# Mirtle_Pico_Hotec_drv8833_pi.net
KiCad netlist of a schematic drawn in EAGLE
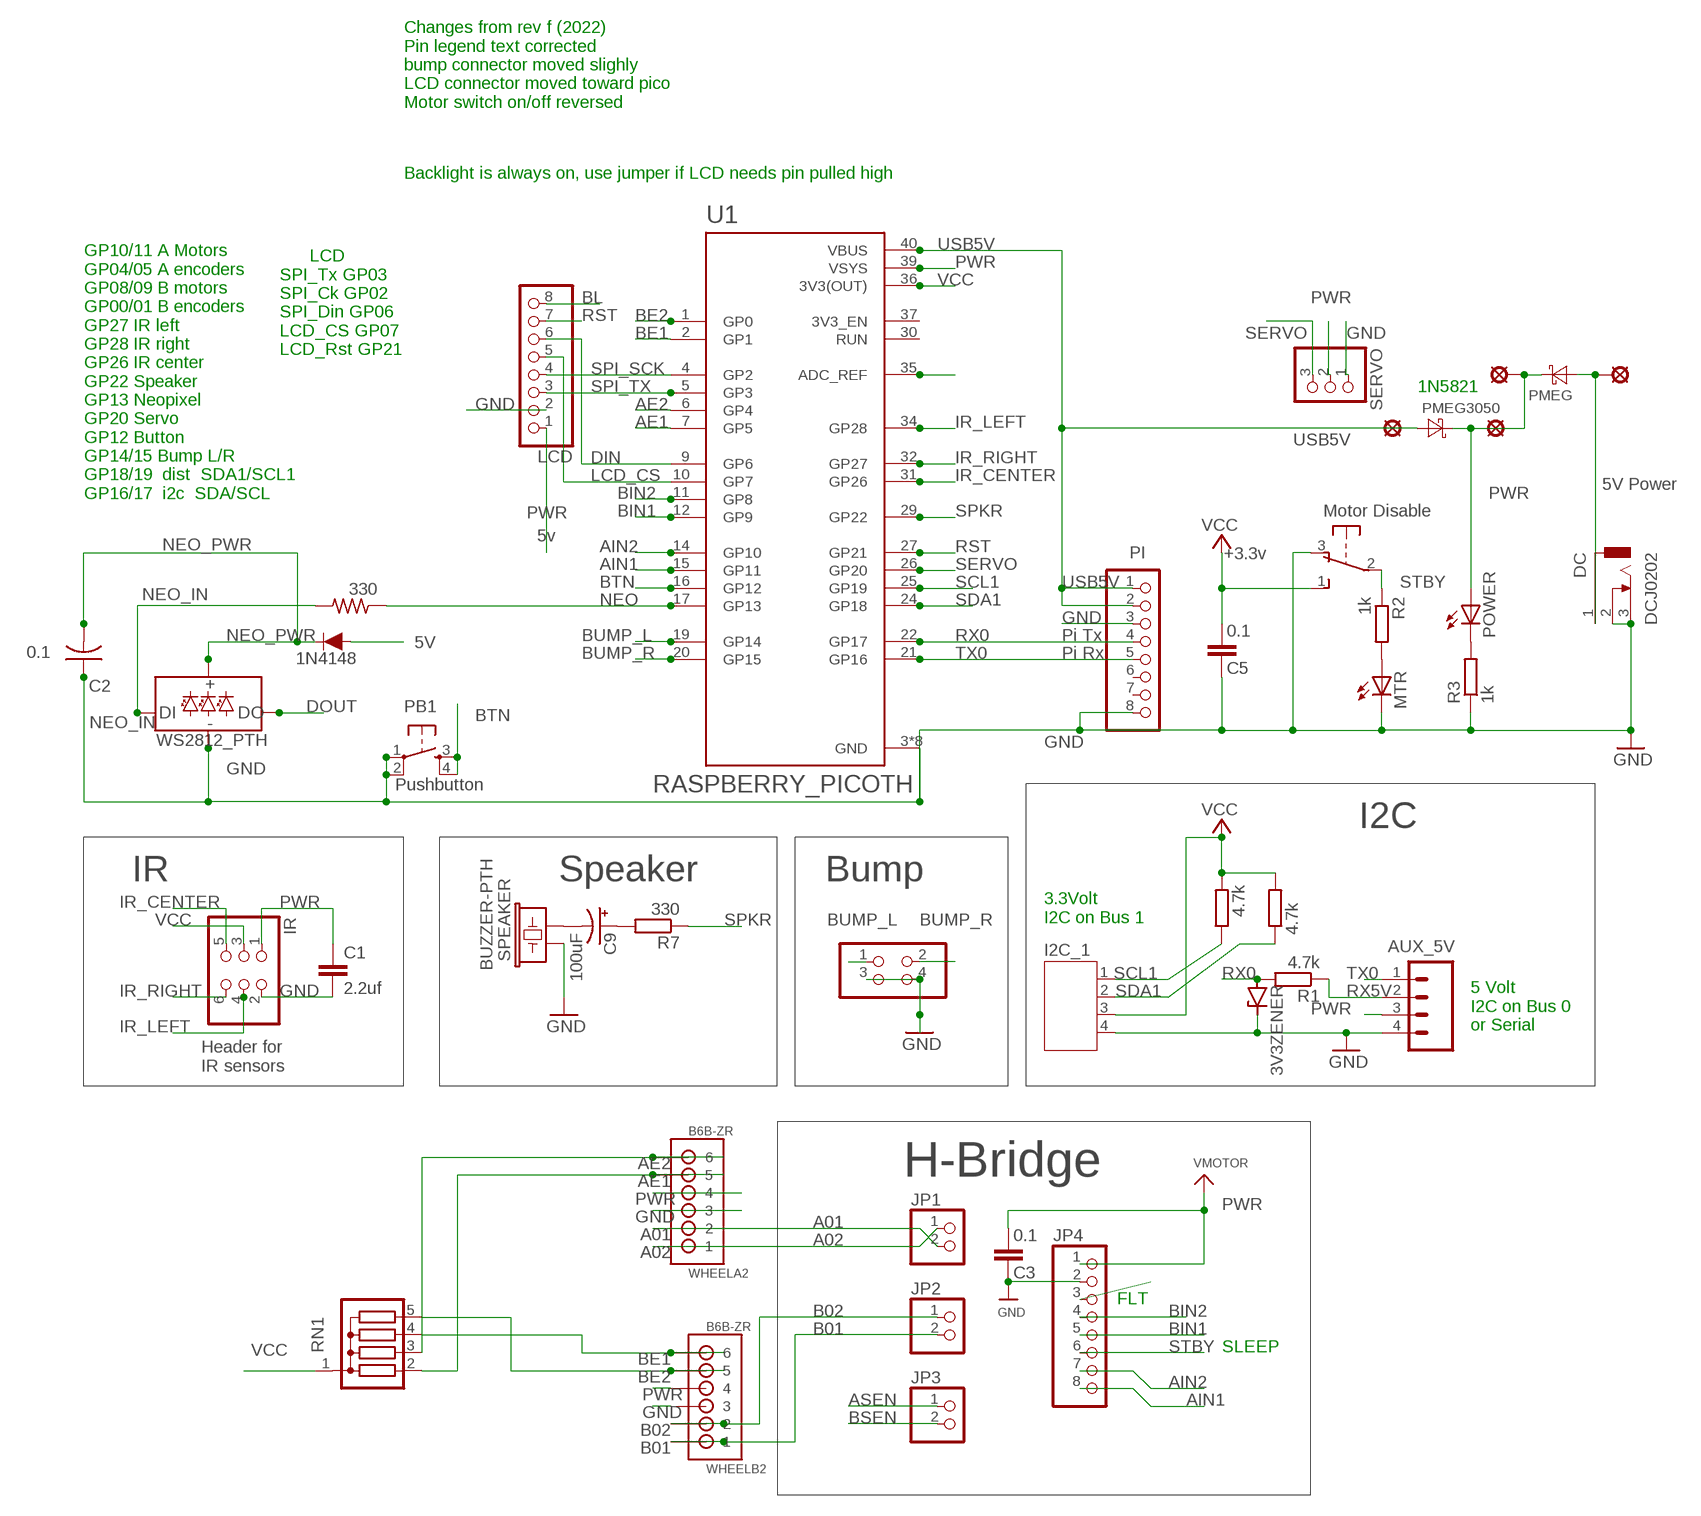
[diagram p0: schematic, sheet 1]

(export (version "E")
  (design (tool "Eeschema 10.0.6"))
  (components
    (comp (ref "3V3ZENER")
      (value "ZENER-DIODEZD-5")
      (footprint "eagle-import:ZDIO-5")
      (libsource (lib "eagle-import") (part "ZENER-DIODEZD-5"))
    )
    (comp (ref "AUX_5V")
      (value "CONN_04")
      (footprint "eagle-import:1X04")
      (libsource (lib "eagle-import") (part "CONN_04"))
    )
    (comp (ref "BUMP")
      (value "PINHD-2X2")
      (footprint "eagle-import:2X02")
      (libsource (lib "eagle-import") (part "PINHD-2X2"))
    )
    (comp (ref "C1")
      (value "2.2uf")
      (footprint "eagle-import:C5B2.5")
      (libsource (lib "eagle-import") (part "C5/2.5"))
    )
    (comp (ref "C2")
      (value "0.1")
      (footprint "eagle-import:C025-024X044")
      (libsource (lib "eagle-import") (part "C-US025-024X044"))
    )
    (comp (ref "C3")
      (value "0.1")
      (footprint "eagle-import:CAP-PTH-SMALLEZ")
      (libsource (lib "eagle-import") (part "CAPEZ"))
    )
    (comp (ref "C5")
      (value "0.1")
      (footprint "eagle-import:CAP-PTH-SMALLEZ")
      (libsource (lib "eagle-import") (part "CAPEZ"))
    )
    (comp (ref "C9")
      (value "100uF")
      (footprint "eagle-import:E2,5-5")
      (libsource (lib "eagle-import") (part "CPOL-USE2.5-5"))
    )
    (comp (ref "D1")
      (value "WS2812_PTH")
      (footprint "eagle-import:WS2812B-PTH-KIT")
      (libsource (lib "eagle-import") (part "WS2812_PTH"))
    )
    (comp (ref "DC")
      (value "DCJ0202")
      (footprint "eagle-import:DCJ0202")
      (libsource (lib "eagle-import") (part "DCJ0202"))
    )
    (comp (ref "I2C_1")
      (value "JST-PH4")
      (footprint "eagle-import:JST-PH4")
      (libsource (lib "eagle-import") (part "JST-PH4"))
    )
    (comp (ref "IN4148")
      (value "200mA/100V/1V")
      (footprint "eagle-import:DIODE-1N4148")
      (libsource (lib "eagle-import") (part "DIODE-1N4148"))
    )
    (comp (ref "IR")
      (value "PINHD-2X3")
      (footprint "eagle-import:2X03")
      (libsource (lib "eagle-import") (part "PINHD-2X3"))
    )
    (comp (ref "JP1")
      (value "HEADER-1X2ROUND")
      (footprint "eagle-import:1X02_ROUND")
      (libsource (lib "eagle-import") (part "HEADER-1X2ROUND"))
    )
    (comp (ref "JP2")
      (value "HEADER-1X2ROUND")
      (footprint "eagle-import:1X02_ROUND")
      (libsource (lib "eagle-import") (part "HEADER-1X2ROUND"))
    )
    (comp (ref "JP3")
      (value "HEADER-1X2ROUND")
      (footprint "eagle-import:1X02_ROUND")
      (libsource (lib "eagle-import") (part "HEADER-1X2ROUND"))
    )
    (comp (ref "JP4")
      (value "HEADER-1X870MIL")
      (footprint "eagle-import:1X08_ROUND_70")
      (libsource (lib "eagle-import") (part "HEADER-1X870MIL"))
    )
    (comp (ref "LCD")
      (value "PINHD-1X8BIG")
      (footprint "eagle-import:1X08-BIG")
      (libsource (lib "eagle-import") (part "PINHD-1X8BIG"))
    )
    (comp (ref "LSP1")
      (value "SE14")
      (footprint "eagle-import:SE14")
      (libsource (lib "eagle-import") (part "SE14"))
    )
    (comp (ref "LSP2")
      (value "SE14")
      (footprint "eagle-import:SE14")
      (libsource (lib "eagle-import") (part "SE14"))
    )
    (comp (ref "LSP3")
      (value "SE14")
      (footprint "eagle-import:SE14")
      (libsource (lib "eagle-import") (part "SE14"))
    )
    (comp (ref "LSP4")
      (value "SE14")
      (footprint "eagle-import:SE14")
      (libsource (lib "eagle-import") (part "SE14"))
    )
    (comp (ref "MTR")
      (value "LED3MM")
      (footprint "eagle-import:LED3MM")
      (libsource (lib "eagle-import") (part "LED3MM"))
    )
    (comp (ref "PB1")
      (value "TAC_SWITCHPTH")
      (footprint "eagle-import:TACTILE-PTH")
      (libsource (lib "eagle-import") (part "TAC_SWITCHPTH"))
    )
    (comp (ref "PI")
      (value "PINHD-1X8BIG")
      (footprint "eagle-import:1X08-BIG")
      (libsource (lib "eagle-import") (part "PINHD-1X8BIG"))
    )
    (comp (ref "PMEG")
      (value "DIODE-SCHOTTKY-SMA")
      (footprint "eagle-import:SMA")
      (libsource (lib "eagle-import") (part "DIODE-SCHOTTKY-SMA"))
    )
    (comp (ref "PMEG3050")
      (value "DIODE-SCHOTTKY-SMA")
      (footprint "eagle-import:SMA")
      (libsource (lib "eagle-import") (part "DIODE-SCHOTTKY-SMA"))
    )
    (comp (ref "POWER")
      (value "LED3MM")
      (footprint "eagle-import:LED3MM")
      (libsource (lib "eagle-import") (part "LED3MM"))
    )
    (comp (ref "R1")
      (value "4.7k")
      (footprint "eagle-import:0204_5")
      (libsource (lib "eagle-import") (part "R-EU_0204/5"))
    )
    (comp (ref "R2")
      (value "1k")
      (footprint "eagle-import:0204_5")
      (libsource (lib "eagle-import") (part "R-EU_0204/5"))
    )
    (comp (ref "R3")
      (value "1k")
      (footprint "eagle-import:0204_5")
      (libsource (lib "eagle-import") (part "R-EU_0204/5"))
    )
    (comp (ref "R4")
      (value "4.7k")
      (footprint "eagle-import:0204_5")
      (libsource (lib "eagle-import") (part "R-EU_0204/5"))
    )
    (comp (ref "R5")
      (value "4.7k")
      (footprint "eagle-import:0204_5")
      (libsource (lib "eagle-import") (part "R-EU_0204/5"))
    )
    (comp (ref "R7")
      (value "330")
      (footprint "eagle-import:0204_5")
      (libsource (lib "eagle-import") (part "R-EU_0204/5"))
    )
    (comp (ref "R12")
      (value "330")
      (footprint "eagle-import:0204_5")
      (libsource (lib "eagle-import") (part "R-US_0204/5"))
    )
    (comp (ref "RN1")
      (value "G04R")
      (footprint "eagle-import:SIL5")
      (libsource (lib "eagle-import") (part "G04R"))
    )
    (comp (ref "SERVO")
      (value "PINHD-1X3")
      (footprint "eagle-import:1X03")
      (libsource (lib "eagle-import") (part "PINHD-1X3"))
    )
    (comp (ref "SPEAKER")
      (value "BUZZER-PTH")
      (footprint "eagle-import:BUZZER-12MM")
      (libsource (lib "eagle-import") (part "BUZZER-PTH"))
    )
    (comp (ref "SW1")
      (value "OS102011MA1Q")
      (footprint "eagle-import:OS102011MA1Q")
      (libsource (lib "eagle-import") (part "OS102011MA1Q"))
    )
    (comp (ref "U1")
      (value "RASPBERRY_PICOTH")
      (footprint "eagle-import:PICO-PKG-TH_MM")
      (libsource (lib "eagle-import") (part "RASPBERRY_PICOTH"))
    )
    (comp (ref "WHEELA2")
      (value "B6B-ZR")
      (footprint "eagle-import:B6B-ZR")
      (libsource (lib "eagle-import") (part "B6B-ZR"))
    )
    (comp (ref "WHEELB2")
      (value "B6B-ZR")
      (footprint "eagle-import:B6B-ZR")
      (libsource (lib "eagle-import") (part "B6B-ZR"))
    )
  )
  (nets
    (net (code "1") (name "/A01") (class "Default")
      (node (ref "JP1") (pin "2") (pinfunction "2_2") (pintype "passive"))
      (node (ref "WHEELA2") (pin "2") (pinfunction "2_2") (pintype "bidirectional"))
    )
    (net (code "2") (name "/A02") (class "Default")
      (node (ref "JP1") (pin "1") (pinfunction "1_1") (pintype "passive"))
      (node (ref "WHEELA2") (pin "1") (pinfunction "1_1") (pintype "bidirectional"))
    )
    (net (code "3") (name "/AE1") (class "Default")
      (node (ref "RN1") (pin "2") (pinfunction "2_2") (pintype "passive"))
      (node (ref "U1") (pin "7") (pinfunction "GP5_7") (pintype "bidirectional"))
      (node (ref "WHEELA2") (pin "5") (pinfunction "5_5") (pintype "bidirectional"))
    )
    (net (code "4") (name "/AE2") (class "Default")
      (node (ref "RN1") (pin "3") (pinfunction "3_3") (pintype "passive"))
      (node (ref "U1") (pin "6") (pinfunction "GP4_6") (pintype "bidirectional"))
      (node (ref "WHEELA2") (pin "6") (pinfunction "6_6") (pintype "bidirectional"))
    )
    (net (code "5") (name "/AIN1") (class "Default")
      (node (ref "JP4") (pin "8") (pinfunction "8_8") (pintype "passive"))
      (node (ref "U1") (pin "15") (pinfunction "GP11_15") (pintype "bidirectional"))
    )
    (net (code "6") (name "/AIN2") (class "Default")
      (node (ref "JP4") (pin "7") (pinfunction "7_7") (pintype "passive"))
      (node (ref "U1") (pin "14") (pinfunction "GP10_14") (pintype "bidirectional"))
    )
    (net (code "7") (name "/ASEN") (class "Default")
      (node (ref "JP3") (pin "1") (pinfunction "1_1") (pintype "passive"))
    )
    (net (code "8") (name "/B01") (class "Default")
      (node (ref "JP2") (pin "2") (pinfunction "2_2") (pintype "passive"))
      (node (ref "WHEELB2") (pin "1") (pinfunction "1_1") (pintype "bidirectional"))
    )
    (net (code "9") (name "/B02") (class "Default")
      (node (ref "JP2") (pin "1") (pinfunction "1_1") (pintype "passive"))
      (node (ref "WHEELB2") (pin "2") (pinfunction "2_2") (pintype "bidirectional"))
    )
    (net (code "10") (name "/BE1") (class "Default")
      (node (ref "RN1") (pin "4") (pinfunction "4_4") (pintype "passive"))
      (node (ref "U1") (pin "2") (pinfunction "GP1_2") (pintype "bidirectional"))
      (node (ref "WHEELB2") (pin "6") (pinfunction "6_6") (pintype "bidirectional"))
    )
    (net (code "11") (name "/BE2") (class "Default")
      (node (ref "RN1") (pin "5") (pinfunction "5_5") (pintype "passive"))
      (node (ref "U1") (pin "1") (pinfunction "GP0_1") (pintype "bidirectional"))
      (node (ref "WHEELB2") (pin "5") (pinfunction "5_5") (pintype "bidirectional"))
    )
    (net (code "12") (name "/BIN1") (class "Default")
      (node (ref "JP4") (pin "5") (pinfunction "5_5") (pintype "passive"))
      (node (ref "U1") (pin "12") (pinfunction "GP9_12") (pintype "bidirectional"))
    )
    (net (code "13") (name "/BIN2") (class "Default")
      (node (ref "JP4") (pin "4") (pinfunction "4_4") (pintype "passive"))
      (node (ref "U1") (pin "11") (pinfunction "GP8_11") (pintype "bidirectional"))
    )
    (net (code "14") (name "/BL") (class "Default")
      (node (ref "LCD") (pin "8") (pinfunction "8_8") (pintype "passive"))
    )
    (net (code "15") (name "/BSEN") (class "Default")
      (node (ref "JP3") (pin "2") (pinfunction "2_2") (pintype "passive"))
    )
    (net (code "16") (name "/BTN") (class "Default")
      (node (ref "PB1") (pin "3") (pinfunction "3_3") (pintype "passive"))
      (node (ref "PB1") (pin "4") (pinfunction "4_4") (pintype "passive"))
      (node (ref "U1") (pin "16") (pinfunction "GP12_16") (pintype "bidirectional"))
    )
    (net (code "17") (name "/BUMP_L") (class "Default")
      (node (ref "BUMP") (pin "1") (pinfunction "1_1") (pintype "passive"))
      (node (ref "U1") (pin "19") (pinfunction "GP14_19") (pintype "bidirectional"))
    )
    (net (code "18") (name "/BUMP_R") (class "Default")
      (node (ref "BUMP") (pin "2") (pinfunction "2_2") (pintype "passive"))
      (node (ref "U1") (pin "20") (pinfunction "GP15_20") (pintype "bidirectional"))
    )
    (net (code "19") (name "/DIN") (class "Default")
      (node (ref "LCD") (pin "6") (pinfunction "6_6") (pintype "passive"))
      (node (ref "U1") (pin "9") (pinfunction "GP6_9") (pintype "bidirectional"))
    )
    (net (code "20") (name "/DOUT") (class "Default")
      (node (ref "D1") (pin "DO") (pinfunction "DO_DO") (pintype "bidirectional"))
    )
    (net (code "21") (name "/IR_CENTER") (class "Default")
      (node (ref "IR") (pin "5") (pinfunction "5_5") (pintype "passive"))
      (node (ref "U1") (pin "31") (pinfunction "GP26_31") (pintype "bidirectional"))
    )
    (net (code "22") (name "/IR_LEFT") (class "Default")
      (node (ref "IR") (pin "4") (pinfunction "4_4") (pintype "passive"))
      (node (ref "U1") (pin "34") (pinfunction "GP28_34") (pintype "bidirectional"))
    )
    (net (code "23") (name "/IR_RIGHT") (class "Default")
      (node (ref "IR") (pin "6") (pinfunction "6_6") (pintype "passive"))
      (node (ref "U1") (pin "32") (pinfunction "GP27_32") (pintype "bidirectional"))
    )
    (net (code "24") (name "/LCD_CS") (class "Default")
      (node (ref "LCD") (pin "5") (pinfunction "5_5") (pintype "passive"))
      (node (ref "U1") (pin "10") (pinfunction "GP7_10") (pintype "bidirectional"))
    )
    (net (code "25") (name "/NEO") (class "Default")
      (node (ref "R12") (pin "1") (pinfunction "1_1") (pintype "passive"))
      (node (ref "U1") (pin "17") (pinfunction "GP13_17") (pintype "bidirectional"))
    )
    (net (code "26") (name "/NEO_IN") (class "Default")
      (node (ref "D1") (pin "DI") (pinfunction "DI_DI") (pintype "bidirectional"))
      (node (ref "R12") (pin "2") (pinfunction "2_2") (pintype "passive"))
    )
    (net (code "27") (name "/NEO_PWR") (class "Default")
      (node (ref "C2") (pin "2") (pinfunction "2_2") (pintype "passive"))
      (node (ref "D1") (pin "VCC") (pinfunction "VCC_VCC") (pintype "bidirectional"))
      (node (ref "IN4148") (pin "C") (pinfunction "C_C") (pintype "passive"))
    )
    (net (code "28") (name "/RST") (class "Default")
      (node (ref "LCD") (pin "7") (pinfunction "7_7") (pintype "passive"))
      (node (ref "U1") (pin "27") (pinfunction "GP21_27") (pintype "bidirectional"))
    )
    (net (code "29") (name "/RX0") (class "Default")
      (node (ref "3V3ZENER") (pin "A") (pinfunction "A_A") (pintype "passive"))
      (node (ref "PI") (pin "4") (pinfunction "4_4") (pintype "passive"))
      (node (ref "R1") (pin "2") (pinfunction "2_2") (pintype "passive"))
      (node (ref "U1") (pin "22") (pinfunction "GP17_22") (pintype "bidirectional"))
    )
    (net (code "30") (name "/RX5V") (class "Default")
      (node (ref "AUX_5V") (pin "2") (pinfunction "2_2") (pintype "passive"))
      (node (ref "R1") (pin "1") (pinfunction "1_1") (pintype "passive"))
    )
    (net (code "31") (name "/SCL1") (class "Default")
      (node (ref "I2C_1") (pin "1") (pinfunction "1_1") (pintype "passive"))
      (node (ref "R5") (pin "1") (pinfunction "1_1") (pintype "passive"))
      (node (ref "U1") (pin "25") (pinfunction "GP19_25") (pintype "bidirectional"))
    )
    (net (code "32") (name "/SDA1") (class "Default")
      (node (ref "I2C_1") (pin "2") (pinfunction "2_2") (pintype "passive"))
      (node (ref "R4") (pin "1") (pinfunction "1_1") (pintype "passive"))
      (node (ref "U1") (pin "24") (pinfunction "GP18_24") (pintype "bidirectional"))
    )
    (net (code "33") (name "/SERVO") (class "Default")
      (node (ref "SERVO") (pin "3") (pinfunction "3_3") (pintype "passive"))
      (node (ref "U1") (pin "26") (pinfunction "GP20_26") (pintype "bidirectional"))
    )
    (net (code "34") (name "/SPI_SCK") (class "Default")
      (node (ref "LCD") (pin "4") (pinfunction "4_4") (pintype "passive"))
      (node (ref "U1") (pin "4") (pinfunction "GP2_4") (pintype "bidirectional"))
    )
    (net (code "35") (name "/SPI_TX") (class "Default")
      (node (ref "LCD") (pin "3") (pinfunction "3_3") (pintype "passive"))
      (node (ref "U1") (pin "5") (pinfunction "GP3_5") (pintype "bidirectional"))
    )
    (net (code "36") (name "/SPKR") (class "Default")
      (node (ref "R7") (pin "1") (pinfunction "1_1") (pintype "passive"))
      (node (ref "U1") (pin "29") (pinfunction "GP22_29") (pintype "bidirectional"))
    )
    (net (code "37") (name "/STBY") (class "Default")
      (node (ref "JP4") (pin "6") (pinfunction "6_6") (pintype "passive"))
      (node (ref "R2") (pin "1") (pinfunction "1_1") (pintype "passive"))
      (node (ref "SW1") (pin "2") (pinfunction "P_2") (pintype "passive"))
    )
    (net (code "38") (name "/TX0") (class "Default")
      (node (ref "AUX_5V") (pin "1") (pinfunction "1_1") (pintype "passive"))
      (node (ref "PI") (pin "5") (pinfunction "5_5") (pintype "passive"))
      (node (ref "U1") (pin "21") (pinfunction "GP16_21") (pintype "bidirectional"))
    )
    (net (code "39") (name "/USB5V") (class "Default")
      (node (ref "LSP1") (pin "MP") (pinfunction "MP_MP") (pintype "passive"))
      (node (ref "PI") (pin "1") (pinfunction "1_1") (pintype "passive"))
      (node (ref "PI") (pin "2") (pinfunction "2_2") (pintype "passive"))
      (node (ref "PMEG3050") (pin "A") (pinfunction "A_A") (pintype "passive"))
      (node (ref "U1") (pin "40") (pinfunction "VBUS_40") (pintype "power_in"))
    )
    (net (code "40") (name "GND") (class "Default")
      (node (ref "3V3ZENER") (pin "C") (pinfunction "C_C") (pintype "passive"))
      (node (ref "AUX_5V") (pin "4") (pinfunction "4_4") (pintype "passive"))
      (node (ref "BUMP") (pin "3") (pinfunction "3_3") (pintype "passive"))
      (node (ref "BUMP") (pin "4") (pinfunction "4_4") (pintype "passive"))
      (node (ref "C1") (pin "2") (pinfunction "2_2") (pintype "passive"))
      (node (ref "C2") (pin "1") (pinfunction "1_1") (pintype "passive"))
      (node (ref "C3") (pin "1") (pinfunction "1_1") (pintype "passive"))
      (node (ref "C5") (pin "1") (pinfunction "1_1") (pintype "passive"))
      (node (ref "D1") (pin "GND") (pinfunction "GND_GND") (pintype "bidirectional"))
      (node (ref "DC") (pin "2") (pinfunction "2_2") (pintype "passive"))
      (node (ref "DC") (pin "3") (pinfunction "3_3") (pintype "passive"))
      (node (ref "I2C_1") (pin "4") (pinfunction "4_4") (pintype "passive"))
      (node (ref "IR") (pin "2") (pinfunction "2_2") (pintype "passive"))
      (node (ref "JP4") (pin "2") (pinfunction "2_2") (pintype "passive"))
      (node (ref "LCD") (pin "2") (pinfunction "2_2") (pintype "passive"))
      (node (ref "MTR") (pin "K") (pinfunction "C_K") (pintype "passive"))
      (node (ref "PB1") (pin "1") (pinfunction "1_1") (pintype "passive"))
      (node (ref "PB1") (pin "2") (pinfunction "2_2") (pintype "passive"))
      (node (ref "PI") (pin "3") (pinfunction "3_3") (pintype "passive"))
      (node (ref "PI") (pin "8") (pinfunction "8_8") (pintype "passive"))
      (node (ref "R3") (pin "1") (pinfunction "1_1") (pintype "passive"))
      (node (ref "SERVO") (pin "1") (pinfunction "1_1") (pintype "passive"))
      (node (ref "SPEAKER") (pin "+") (pinfunction "1_+") (pintype "passive"))
      (node (ref "SW1") (pin "3") (pinfunction "O_3") (pintype "passive"))
      (node (ref "U1") (pin "13") (pinfunction "GND_13") (pintype "power_in"))
      (node (ref "U1") (pin "18") (pinfunction "GND_18") (pintype "power_in"))
      (node (ref "U1") (pin "23") (pinfunction "GND_23") (pintype "power_in"))
      (node (ref "U1") (pin "28") (pinfunction "GND_28") (pintype "power_in"))
      (node (ref "U1") (pin "3") (pinfunction "GND_3") (pintype "power_in"))
      (node (ref "U1") (pin "33") (pinfunction "GND_33") (pintype "power_in"))
      (node (ref "U1") (pin "38") (pinfunction "GND_38") (pintype "power_in"))
      (node (ref "U1") (pin "8") (pinfunction "GND_8") (pintype "power_in"))
      (node (ref "WHEELA2") (pin "3") (pinfunction "3_3") (pintype "bidirectional"))
      (node (ref "WHEELB2") (pin "3") (pinfunction "3_3") (pintype "bidirectional"))
    )
    (net (code "41") (name "Net-(C9-Pad+)") (class "Default")
      (node (ref "C9") (pin "+") (pinfunction "+_+") (pintype "passive"))
      (node (ref "R7") (pin "2") (pinfunction "2_2") (pintype "passive"))
    )
    (net (code "42") (name "Net-(DC-Pad1)") (class "Default")
      (node (ref "DC") (pin "1") (pinfunction "1_1") (pintype "passive"))
      (node (ref "LSP3") (pin "MP") (pinfunction "MP_MP") (pintype "passive"))
      (node (ref "PMEG") (pin "A") (pinfunction "A_A") (pintype "passive"))
    )
    (net (code "43") (name "Net-(MTR-PadA)") (class "Default")
      (node (ref "MTR") (pin "A") (pinfunction "A_A") (pintype "passive"))
      (node (ref "R2") (pin "2") (pinfunction "2_2") (pintype "passive"))
    )
    (net (code "44") (name "Net-(POWER-C)") (class "Default")
      (node (ref "POWER") (pin "K") (pinfunction "C_K") (pintype "passive"))
      (node (ref "R3") (pin "2") (pinfunction "2_2") (pintype "passive"))
    )
    (net (code "45") (name "Net-(SPEAKER-2)") (class "Default")
      (node (ref "C9") (pin "-") (pinfunction "-_-") (pintype "passive"))
      (node (ref "SPEAKER") (pin "-") (pinfunction "2_-") (pintype "passive"))
    )
    (net (code "46") (name "VCC") (class "Default")
      (node (ref "C5") (pin "2") (pinfunction "2_2") (pintype "passive"))
      (node (ref "I2C_1") (pin "3") (pinfunction "3_3") (pintype "passive"))
      (node (ref "IR") (pin "3") (pinfunction "3_3") (pintype "passive"))
      (node (ref "R4") (pin "2") (pinfunction "2_2") (pintype "passive"))
      (node (ref "R5") (pin "2") (pinfunction "2_2") (pintype "passive"))
      (node (ref "RN1") (pin "1") (pinfunction "1_1") (pintype "passive"))
      (node (ref "SW1") (pin "1") (pinfunction "S_1") (pintype "passive"))
      (node (ref "U1") (pin "36") (pinfunction "3V3(OUT)_36") (pintype "power_in"))
    )
    (net (code "47") (name "VMOTOR") (class "Default")
      (node (ref "AUX_5V") (pin "3") (pinfunction "3_3") (pintype "passive"))
      (node (ref "C1") (pin "1") (pinfunction "1_1") (pintype "passive"))
      (node (ref "C3") (pin "2") (pinfunction "2_2") (pintype "passive"))
      (node (ref "IN4148") (pin "A") (pinfunction "A_A") (pintype "passive"))
      (node (ref "IR") (pin "1") (pinfunction "1_1") (pintype "passive"))
      (node (ref "JP4") (pin "1") (pinfunction "1_1") (pintype "passive"))
      (node (ref "LCD") (pin "1") (pinfunction "1_1") (pintype "passive"))
      (node (ref "LSP2") (pin "MP") (pinfunction "MP_MP") (pintype "passive"))
      (node (ref "LSP4") (pin "MP") (pinfunction "MP_MP") (pintype "passive"))
      (node (ref "PMEG") (pin "C") (pinfunction "C_C") (pintype "passive"))
      (node (ref "PMEG3050") (pin "C") (pinfunction "C_C") (pintype "passive"))
      (node (ref "POWER") (pin "A") (pinfunction "A_A") (pintype "passive"))
      (node (ref "SERVO") (pin "2") (pinfunction "2_2") (pintype "passive"))
      (node (ref "U1") (pin "39") (pinfunction "VSYS_39") (pintype "power_in"))
      (node (ref "WHEELA2") (pin "4") (pinfunction "4_4") (pintype "bidirectional"))
      (node (ref "WHEELB2") (pin "4") (pinfunction "4_4") (pintype "bidirectional"))
    )
    (net (code "48") (name "unconnected-(JP4-Pad3)") (class "Default")
      (node (ref "JP4") (pin "3") (pinfunction "3_3") (pintype "passive"))
    )
    (net (code "49") (name "unconnected-(PI-Pad6)") (class "Default")
      (node (ref "PI") (pin "6") (pinfunction "6_6") (pintype "passive"))
    )
    (net (code "50") (name "unconnected-(PI-Pad7)") (class "Default")
      (node (ref "PI") (pin "7") (pinfunction "7_7") (pintype "passive"))
    )
    (net (code "51") (name "unconnected-(U1-3V3_EN-Pad37)") (class "Default")
      (node (ref "U1") (pin "37") (pinfunction "3V3_EN_37") (pintype "input"))
    )
    (net (code "52") (name "unconnected-(U1-ADC_REF-Pad35)") (class "Default")
      (node (ref "U1") (pin "35") (pinfunction "ADC_REF_35") (pintype "input"))
    )
    (net (code "53") (name "unconnected-(U1-RUN-Pad30)") (class "Default")
      (node (ref "U1") (pin "30") (pinfunction "RUN_30") (pintype "input"))
    )
  )
)
